# hat_v1.net
KiCad netlist of a schematic drawn in EAGLE
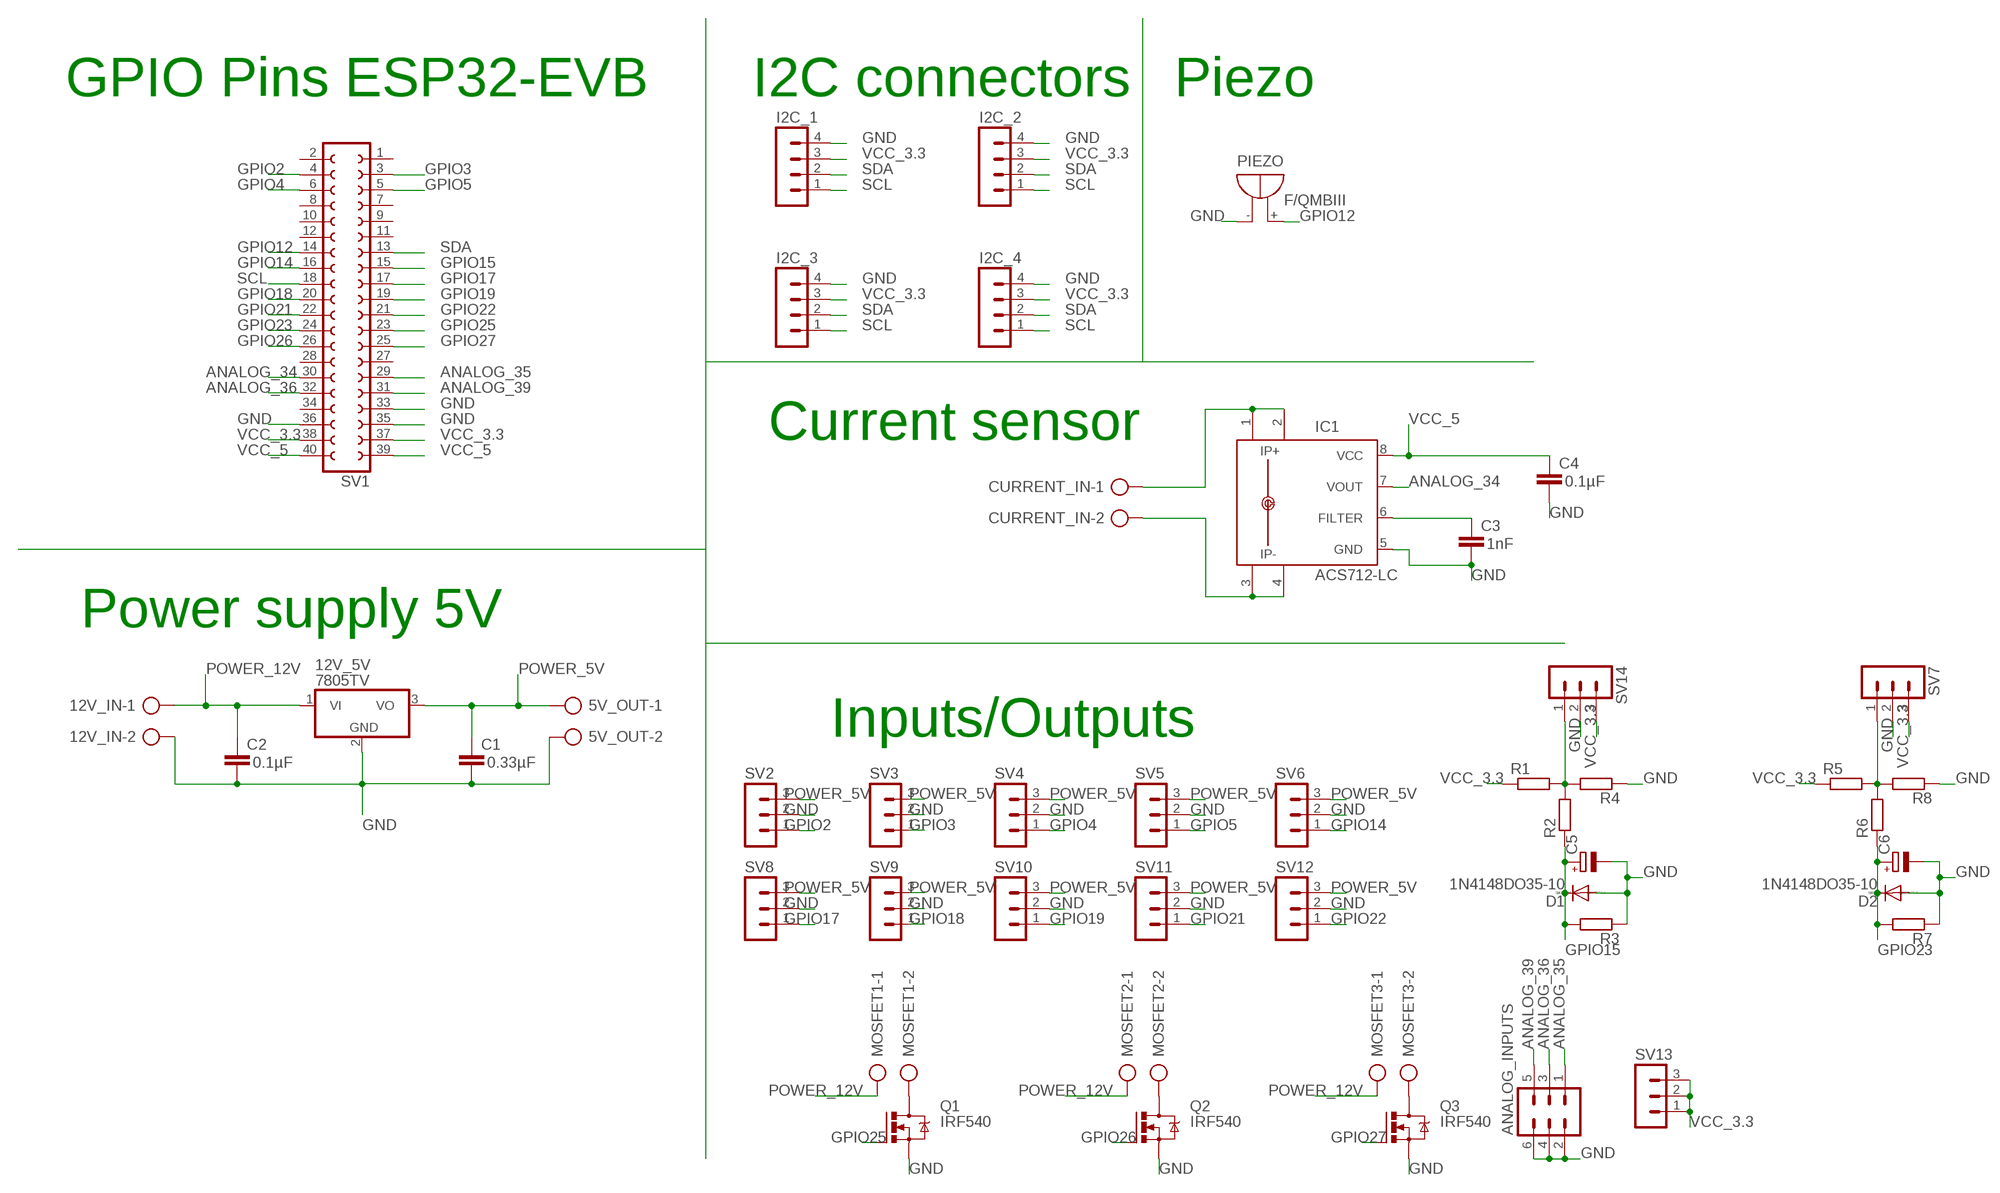
[diagram p0: schematic, sheet 1]

(export (version "E")
  (design (tool "Eeschema 10.0.6"))
  (components
    (comp (ref "5V_OUT")
      (value "AK500/2")
      (footprint "eagle-import:AK500_2")
      (libsource (lib "eagle-import") (part "AK500/2"))
    )
    (comp (ref "12V_5V")
      (value "7805TV")
      (footprint "eagle-import:TO220V")
      (libsource (lib "eagle-import") (part "78TV05"))
    )
    (comp (ref "12V_IN")
      (value "AK500/2")
      (footprint "eagle-import:AK500_2")
      (libsource (lib "eagle-import") (part "AK500/2"))
    )
    (comp (ref "ANALOG_INPUTS")
      (value "MA03-2")
      (footprint "eagle-import:MA03-2")
      (libsource (lib "eagle-import") (part "MA03-2"))
    )
    (comp (ref "C1")
      (value "C-EU050-050X075")
      (footprint "eagle-import:C050-050X075")
      (fields (field (name "C1") "0.33µF"))
      (libsource (lib "eagle-import") (part "resistor_348_C-EU050-050X075"))
    )
    (comp (ref "C2")
      (value "C-EU050-035X075")
      (footprint "eagle-import:C050-035X075")
      (fields (field (name "C2") "0.1µF"))
      (libsource (lib "eagle-import") (part "resistor_348_C-EU050-035X075"))
    )
    (comp (ref "C3")
      (value "C-EU025-025X050")
      (footprint "eagle-import:C025-025X050")
      (fields (field (name "SPICEPREFIX") "C") (field (name "SPICEPREFIX_1") "1nF"))
      (libsource (lib "eagle-import") (part "C-EU025-025X050"))
    )
    (comp (ref "C4")
      (value "C-EU025-025X050")
      (footprint "eagle-import:C025-025X050")
      (fields (field (name "SPICEPREFIX") "C") (field (name "SPICEPREFIX_1") "0.1µF"))
      (libsource (lib "eagle-import") (part "C-EU025-025X050"))
    )
    (comp (ref "C5")
      (value "CPOL-EUE2.5-6")
      (footprint "eagle-import:E2,5-6")
      (libsource (lib "eagle-import") (part "CPOL-EUE2.5-6"))
    )
    (comp (ref "C6")
      (value "CPOL-EUE2.5-6")
      (footprint "eagle-import:E2,5-6")
      (libsource (lib "eagle-import") (part "CPOL-EUE2.5-6"))
    )
    (comp (ref "CURRENT_IN")
      (value "AK500/2")
      (footprint "eagle-import:AK500_2")
      (libsource (lib "eagle-import") (part "AK500/2"))
    )
    (comp (ref "D1")
      (value "1N4148DO35-10")
      (footprint "eagle-import:DO35-10")
      (libsource (lib "eagle-import") (part "1N4148DO35-10"))
    )
    (comp (ref "D2")
      (value "1N4148DO35-10")
      (footprint "eagle-import:DO35-10")
      (libsource (lib "eagle-import") (part "1N4148DO35-10"))
    )
    (comp (ref "I2C_1")
      (value "MA04-1")
      (footprint "eagle-import:MA04-1")
      (libsource (lib "eagle-import") (part "MA04-1"))
    )
    (comp (ref "I2C_2")
      (value "MA04-1")
      (footprint "eagle-import:MA04-1")
      (libsource (lib "eagle-import") (part "MA04-1"))
    )
    (comp (ref "I2C_3")
      (value "MA04-1")
      (footprint "eagle-import:MA04-1")
      (libsource (lib "eagle-import") (part "MA04-1"))
    )
    (comp (ref "I2C_4")
      (value "MA04-1")
      (footprint "eagle-import:MA04-1")
      (libsource (lib "eagle-import") (part "MA04-1"))
    )
    (comp (ref "IC1")
      (value "ACS712-LC")
      (footprint "eagle-import:SOIC8")
      (libsource (lib "eagle-import") (part "ACS712-LC"))
    )
    (comp (ref "MOSFET1")
      (value "AK500/2")
      (footprint "eagle-import:AK500_2")
      (libsource (lib "eagle-import") (part "AK500/2"))
    )
    (comp (ref "MOSFET2")
      (value "AK500/2")
      (footprint "eagle-import:AK500_2")
      (libsource (lib "eagle-import") (part "AK500/2"))
    )
    (comp (ref "MOSFET3")
      (value "AK500/2")
      (footprint "eagle-import:AK500_2")
      (libsource (lib "eagle-import") (part "AK500/2"))
    )
    (comp (ref "PIEZO")
      (value "F/QMBIII")
      (footprint "eagle-import:F_QMBIII")
      (libsource (lib "eagle-import") (part "F/QMBIII"))
    )
    (comp (ref "Q1")
      (value "IRF540")
      (footprint "eagle-import:TO220BV")
      (libsource (lib "eagle-import") (part "IRF540"))
    )
    (comp (ref "Q2")
      (value "IRF540")
      (footprint "eagle-import:TO220BV")
      (libsource (lib "eagle-import") (part "IRF540"))
    )
    (comp (ref "Q3")
      (value "IRF540")
      (footprint "eagle-import:TO220BV")
      (libsource (lib "eagle-import") (part "IRF540"))
    )
    (comp (ref "R1")
      (value "R-EU_0207/2V")
      (footprint "eagle-import:0207_2V")
      (libsource (lib "eagle-import") (part "R-EU_0207/2V"))
    )
    (comp (ref "R2")
      (value "R-EU_0207/2V")
      (footprint "eagle-import:0207_2V")
      (libsource (lib "eagle-import") (part "R-EU_0207/2V"))
    )
    (comp (ref "R3")
      (value "R-EU_0207/2V")
      (footprint "eagle-import:0207_2V")
      (libsource (lib "eagle-import") (part "R-EU_0207/2V"))
    )
    (comp (ref "R4")
      (value "R-EU_0617/5V")
      (footprint "eagle-import:0617V")
      (libsource (lib "eagle-import") (part "R-EU_0617/5V"))
    )
    (comp (ref "R5")
      (value "R-EU_0207/2V")
      (footprint "eagle-import:0207_2V")
      (libsource (lib "eagle-import") (part "R-EU_0207/2V"))
    )
    (comp (ref "R6")
      (value "R-EU_0207/2V")
      (footprint "eagle-import:0207_2V")
      (libsource (lib "eagle-import") (part "R-EU_0207/2V"))
    )
    (comp (ref "R7")
      (value "R-EU_0207/2V")
      (footprint "eagle-import:0207_2V")
      (libsource (lib "eagle-import") (part "R-EU_0207/2V"))
    )
    (comp (ref "R8")
      (value "R-EU_0617/5V")
      (footprint "eagle-import:0617V")
      (libsource (lib "eagle-import") (part "R-EU_0617/5V"))
    )
    (comp (ref "SV1")
      (value "FE20-2")
      (footprint "eagle-import:FE20-2")
      (libsource (lib "eagle-import") (part "FE20-2"))
    )
    (comp (ref "SV2")
      (value "MA03-1")
      (footprint "eagle-import:MA03-1")
      (libsource (lib "eagle-import") (part "MA03-1"))
    )
    (comp (ref "SV3")
      (value "MA03-1")
      (footprint "eagle-import:MA03-1")
      (fields (field (name "SPICEPREFIX") "J"))
      (libsource (lib "eagle-import") (part "MA03-1"))
    )
    (comp (ref "SV4")
      (value "MA03-1")
      (footprint "eagle-import:MA03-1")
      (fields (field (name "SPICEPREFIX") "J"))
      (libsource (lib "eagle-import") (part "MA03-1"))
    )
    (comp (ref "SV5")
      (value "MA03-1")
      (footprint "eagle-import:MA03-1")
      (fields (field (name "SPICEPREFIX") "J"))
      (libsource (lib "eagle-import") (part "MA03-1"))
    )
    (comp (ref "SV6")
      (value "MA03-1")
      (footprint "eagle-import:MA03-1")
      (fields (field (name "SPICEPREFIX") "J"))
      (libsource (lib "eagle-import") (part "MA03-1"))
    )
    (comp (ref "SV7")
      (value "MA03-1")
      (footprint "eagle-import:MA03-1")
      (fields (field (name "SPICEPREFIX") "J"))
      (libsource (lib "eagle-import") (part "MA03-1"))
    )
    (comp (ref "SV8")
      (value "MA03-1")
      (footprint "eagle-import:MA03-1")
      (libsource (lib "eagle-import") (part "MA03-1"))
    )
    (comp (ref "SV9")
      (value "MA03-1")
      (footprint "eagle-import:MA03-1")
      (fields (field (name "SPICEPREFIX") "J"))
      (libsource (lib "eagle-import") (part "MA03-1"))
    )
    (comp (ref "SV10")
      (value "MA03-1")
      (footprint "eagle-import:MA03-1")
      (fields (field (name "SPICEPREFIX") "J"))
      (libsource (lib "eagle-import") (part "MA03-1"))
    )
    (comp (ref "SV11")
      (value "MA03-1")
      (footprint "eagle-import:MA03-1")
      (fields (field (name "SPICEPREFIX") "J"))
      (libsource (lib "eagle-import") (part "MA03-1"))
    )
    (comp (ref "SV12")
      (value "MA03-1")
      (footprint "eagle-import:MA03-1")
      (fields (field (name "SPICEPREFIX") "J"))
      (libsource (lib "eagle-import") (part "MA03-1"))
    )
    (comp (ref "SV13")
      (value "MA03-1")
      (footprint "eagle-import:MA03-1")
      (libsource (lib "eagle-import") (part "MA03-1"))
    )
    (comp (ref "SV14")
      (value "MA03-1")
      (footprint "eagle-import:MA03-1")
      (fields (field (name "SPICEPREFIX") "J"))
      (libsource (lib "eagle-import") (part "MA03-1"))
    )
  )
  (nets
    (net (code "1") (name "/ANALOG_34") (class "Default")
      (node (ref "IC1") (pin "7") (pinfunction "VOUT_7") (pintype "output"))
      (node (ref "SV1") (pin "30") (pinfunction "30_30") (pintype "passive"))
    )
    (net (code "2") (name "/ANALOG_35") (class "Default")
      (node (ref "ANALOG_INPUTS") (pin "1") (pinfunction "1_1") (pintype "passive"))
      (node (ref "SV1") (pin "29") (pinfunction "29_29") (pintype "passive"))
    )
    (net (code "3") (name "/ANALOG_36") (class "Default")
      (node (ref "ANALOG_INPUTS") (pin "3") (pinfunction "3_3") (pintype "passive"))
      (node (ref "SV1") (pin "32") (pinfunction "32_32") (pintype "passive"))
    )
    (net (code "4") (name "/ANALOG_39") (class "Default")
      (node (ref "ANALOG_INPUTS") (pin "5") (pinfunction "5_5") (pintype "passive"))
      (node (ref "SV1") (pin "31") (pinfunction "31_31") (pintype "passive"))
    )
    (net (code "5") (name "/GND") (class "Default")
      (node (ref "12V_5V") (pin "2") (pinfunction "GND_2") (pintype "passive"))
      (node (ref "12V_IN") (pin "2") (pinfunction "KL_2") (pintype "passive"))
      (node (ref "5V_OUT") (pin "2") (pinfunction "KL_2") (pintype "passive"))
      (node (ref "ANALOG_INPUTS") (pin "2") (pinfunction "2_2") (pintype "passive"))
      (node (ref "ANALOG_INPUTS") (pin "4") (pinfunction "4_4") (pintype "passive"))
      (node (ref "ANALOG_INPUTS") (pin "6") (pinfunction "6_6") (pintype "passive"))
      (node (ref "C1") (pin "2") (pinfunction "2_2") (pintype "passive"))
      (node (ref "C2") (pin "2") (pinfunction "2_2") (pintype "passive"))
      (node (ref "C3") (pin "2") (pinfunction "2_2") (pintype "passive"))
      (node (ref "C4") (pin "2") (pinfunction "2_2") (pintype "passive"))
      (node (ref "C5") (pin "-") (pinfunction "-_-") (pintype "passive"))
      (node (ref "C6") (pin "-") (pinfunction "-_-") (pintype "passive"))
      (node (ref "D1") (pin "A") (pinfunction "A_A") (pintype "passive"))
      (node (ref "D2") (pin "A") (pinfunction "A_A") (pintype "passive"))
      (node (ref "I2C_1") (pin "4") (pinfunction "4_4") (pintype "passive"))
      (node (ref "I2C_2") (pin "4") (pinfunction "4_4") (pintype "passive"))
      (node (ref "I2C_3") (pin "4") (pinfunction "4_4") (pintype "passive"))
      (node (ref "I2C_4") (pin "4") (pinfunction "4_4") (pintype "passive"))
      (node (ref "IC1") (pin "5") (pinfunction "GND_5") (pintype "power_in"))
      (node (ref "PIEZO") (pin "-") (pinfunction "+_-") (pintype "passive"))
      (node (ref "Q1") (pin "S") (pinfunction "S_S") (pintype "passive"))
      (node (ref "Q2") (pin "S") (pinfunction "S_S") (pintype "passive"))
      (node (ref "Q3") (pin "S") (pinfunction "S_S") (pintype "passive"))
      (node (ref "R3") (pin "1") (pinfunction "1_1") (pintype "passive"))
      (node (ref "R4") (pin "1") (pinfunction "1_1") (pintype "passive"))
      (node (ref "R7") (pin "1") (pinfunction "1_1") (pintype "passive"))
      (node (ref "R8") (pin "1") (pinfunction "1_1") (pintype "passive"))
      (node (ref "SV1") (pin "33") (pinfunction "33_33") (pintype "passive"))
      (node (ref "SV1") (pin "35") (pinfunction "35_35") (pintype "passive"))
      (node (ref "SV1") (pin "36") (pinfunction "36_36") (pintype "passive"))
      (node (ref "SV10") (pin "2") (pinfunction "2_2") (pintype "passive"))
      (node (ref "SV11") (pin "2") (pinfunction "2_2") (pintype "passive"))
      (node (ref "SV12") (pin "2") (pinfunction "2_2") (pintype "passive"))
      (node (ref "SV14") (pin "2") (pinfunction "2_2") (pintype "passive"))
      (node (ref "SV2") (pin "2") (pinfunction "2_2") (pintype "passive"))
      (node (ref "SV3") (pin "2") (pinfunction "2_2") (pintype "passive"))
      (node (ref "SV4") (pin "2") (pinfunction "2_2") (pintype "passive"))
      (node (ref "SV5") (pin "2") (pinfunction "2_2") (pintype "passive"))
      (node (ref "SV6") (pin "2") (pinfunction "2_2") (pintype "passive"))
      (node (ref "SV7") (pin "2") (pinfunction "2_2") (pintype "passive"))
      (node (ref "SV8") (pin "2") (pinfunction "2_2") (pintype "passive"))
      (node (ref "SV9") (pin "2") (pinfunction "2_2") (pintype "passive"))
    )
    (net (code "6") (name "/GPIO2") (class "Default")
      (node (ref "SV1") (pin "4") (pinfunction "4_4") (pintype "passive"))
      (node (ref "SV2") (pin "1") (pinfunction "1_1") (pintype "passive"))
    )
    (net (code "7") (name "/GPIO3") (class "Default")
      (node (ref "SV1") (pin "3") (pinfunction "3_3") (pintype "passive"))
      (node (ref "SV3") (pin "1") (pinfunction "1_1") (pintype "passive"))
    )
    (net (code "8") (name "/GPIO4") (class "Default")
      (node (ref "SV1") (pin "6") (pinfunction "6_6") (pintype "passive"))
      (node (ref "SV4") (pin "1") (pinfunction "1_1") (pintype "passive"))
    )
    (net (code "9") (name "/GPIO5") (class "Default")
      (node (ref "SV1") (pin "5") (pinfunction "5_5") (pintype "passive"))
      (node (ref "SV5") (pin "1") (pinfunction "1_1") (pintype "passive"))
    )
    (net (code "10") (name "/GPIO12") (class "Default")
      (node (ref "PIEZO") (pin "+") (pinfunction "-_+") (pintype "passive"))
      (node (ref "SV1") (pin "14") (pinfunction "14_14") (pintype "passive"))
    )
    (net (code "11") (name "/GPIO14") (class "Default")
      (node (ref "SV1") (pin "16") (pinfunction "16_16") (pintype "passive"))
      (node (ref "SV6") (pin "1") (pinfunction "1_1") (pintype "passive"))
    )
    (net (code "12") (name "/GPIO15") (class "Default")
      (node (ref "C5") (pin "+") (pinfunction "+_+") (pintype "passive"))
      (node (ref "D1") (pin "C") (pinfunction "C_C") (pintype "passive"))
      (node (ref "R2") (pin "1") (pinfunction "1_1") (pintype "passive"))
      (node (ref "R3") (pin "2") (pinfunction "2_2") (pintype "passive"))
      (node (ref "SV1") (pin "15") (pinfunction "15_15") (pintype "passive"))
    )
    (net (code "13") (name "/GPIO17") (class "Default")
      (node (ref "SV1") (pin "17") (pinfunction "17_17") (pintype "passive"))
      (node (ref "SV8") (pin "1") (pinfunction "1_1") (pintype "passive"))
    )
    (net (code "14") (name "/GPIO18") (class "Default")
      (node (ref "SV1") (pin "20") (pinfunction "20_20") (pintype "passive"))
      (node (ref "SV9") (pin "1") (pinfunction "1_1") (pintype "passive"))
    )
    (net (code "15") (name "/GPIO19") (class "Default")
      (node (ref "SV1") (pin "19") (pinfunction "19_19") (pintype "passive"))
      (node (ref "SV10") (pin "1") (pinfunction "1_1") (pintype "passive"))
    )
    (net (code "16") (name "/GPIO21") (class "Default")
      (node (ref "SV1") (pin "22") (pinfunction "22_22") (pintype "passive"))
      (node (ref "SV11") (pin "1") (pinfunction "1_1") (pintype "passive"))
    )
    (net (code "17") (name "/GPIO22") (class "Default")
      (node (ref "SV1") (pin "21") (pinfunction "21_21") (pintype "passive"))
      (node (ref "SV12") (pin "1") (pinfunction "1_1") (pintype "passive"))
    )
    (net (code "18") (name "/GPIO23") (class "Default")
      (node (ref "C6") (pin "+") (pinfunction "+_+") (pintype "passive"))
      (node (ref "D2") (pin "C") (pinfunction "C_C") (pintype "passive"))
      (node (ref "R6") (pin "1") (pinfunction "1_1") (pintype "passive"))
      (node (ref "R7") (pin "2") (pinfunction "2_2") (pintype "passive"))
      (node (ref "SV1") (pin "24") (pinfunction "24_24") (pintype "passive"))
    )
    (net (code "19") (name "/GPIO25") (class "Default")
      (node (ref "Q1") (pin "G") (pinfunction "G_G") (pintype "passive"))
      (node (ref "SV1") (pin "23") (pinfunction "23_23") (pintype "passive"))
    )
    (net (code "20") (name "/GPIO26") (class "Default")
      (node (ref "Q2") (pin "G") (pinfunction "G_G") (pintype "passive"))
      (node (ref "SV1") (pin "26") (pinfunction "26_26") (pintype "passive"))
    )
    (net (code "21") (name "/GPIO27") (class "Default")
      (node (ref "Q3") (pin "G") (pinfunction "G_G") (pintype "passive"))
      (node (ref "SV1") (pin "25") (pinfunction "25_25") (pintype "passive"))
    )
    (net (code "22") (name "/POWER_5V") (class "Default")
      (node (ref "12V_5V") (pin "3") (pinfunction "VO_3") (pintype "passive"))
      (node (ref "5V_OUT") (pin "1") (pinfunction "KL_1") (pintype "passive"))
      (node (ref "C1") (pin "1") (pinfunction "1_1") (pintype "passive"))
      (node (ref "SV10") (pin "3") (pinfunction "3_3") (pintype "passive"))
      (node (ref "SV11") (pin "3") (pinfunction "3_3") (pintype "passive"))
      (node (ref "SV12") (pin "3") (pinfunction "3_3") (pintype "passive"))
      (node (ref "SV2") (pin "3") (pinfunction "3_3") (pintype "passive"))
      (node (ref "SV3") (pin "3") (pinfunction "3_3") (pintype "passive"))
      (node (ref "SV4") (pin "3") (pinfunction "3_3") (pintype "passive"))
      (node (ref "SV5") (pin "3") (pinfunction "3_3") (pintype "passive"))
      (node (ref "SV6") (pin "3") (pinfunction "3_3") (pintype "passive"))
      (node (ref "SV8") (pin "3") (pinfunction "3_3") (pintype "passive"))
      (node (ref "SV9") (pin "3") (pinfunction "3_3") (pintype "passive"))
    )
    (net (code "23") (name "/POWER_12V") (class "Default")
      (node (ref "12V_5V") (pin "1") (pinfunction "VI_1") (pintype "input"))
      (node (ref "12V_IN") (pin "1") (pinfunction "KL_1") (pintype "passive"))
      (node (ref "C2") (pin "1") (pinfunction "1_1") (pintype "passive"))
      (node (ref "MOSFET1") (pin "1") (pinfunction "KL_1") (pintype "passive"))
      (node (ref "MOSFET2") (pin "1") (pinfunction "KL_1") (pintype "passive"))
      (node (ref "MOSFET3") (pin "1") (pinfunction "KL_1") (pintype "passive"))
    )
    (net (code "24") (name "/SCL") (class "Default")
      (node (ref "I2C_1") (pin "1") (pinfunction "1_1") (pintype "passive"))
      (node (ref "I2C_2") (pin "1") (pinfunction "1_1") (pintype "passive"))
      (node (ref "I2C_3") (pin "1") (pinfunction "1_1") (pintype "passive"))
      (node (ref "I2C_4") (pin "1") (pinfunction "1_1") (pintype "passive"))
      (node (ref "SV1") (pin "18") (pinfunction "18_18") (pintype "passive"))
    )
    (net (code "25") (name "/SDA") (class "Default")
      (node (ref "I2C_1") (pin "2") (pinfunction "2_2") (pintype "passive"))
      (node (ref "I2C_2") (pin "2") (pinfunction "2_2") (pintype "passive"))
      (node (ref "I2C_3") (pin "2") (pinfunction "2_2") (pintype "passive"))
      (node (ref "I2C_4") (pin "2") (pinfunction "2_2") (pintype "passive"))
      (node (ref "SV1") (pin "13") (pinfunction "13_13") (pintype "passive"))
    )
    (net (code "26") (name "/VCC_3.3") (class "Default")
      (node (ref "I2C_1") (pin "3") (pinfunction "3_3") (pintype "passive"))
      (node (ref "I2C_2") (pin "3") (pinfunction "3_3") (pintype "passive"))
      (node (ref "I2C_3") (pin "3") (pinfunction "3_3") (pintype "passive"))
      (node (ref "I2C_4") (pin "3") (pinfunction "3_3") (pintype "passive"))
      (node (ref "R1") (pin "1") (pinfunction "1_1") (pintype "passive"))
      (node (ref "R5") (pin "1") (pinfunction "1_1") (pintype "passive"))
      (node (ref "SV1") (pin "37") (pinfunction "37_37") (pintype "passive"))
      (node (ref "SV1") (pin "38") (pinfunction "38_38") (pintype "passive"))
      (node (ref "SV13") (pin "1") (pinfunction "1_1") (pintype "passive"))
      (node (ref "SV13") (pin "2") (pinfunction "2_2") (pintype "passive"))
      (node (ref "SV13") (pin "3") (pinfunction "3_3") (pintype "passive"))
      (node (ref "SV14") (pin "3") (pinfunction "3_3") (pintype "passive"))
      (node (ref "SV7") (pin "3") (pinfunction "3_3") (pintype "passive"))
    )
    (net (code "27") (name "/VCC_5") (class "Default")
      (node (ref "C4") (pin "1") (pinfunction "1_1") (pintype "passive"))
      (node (ref "IC1") (pin "8") (pinfunction "VCC_8") (pintype "power_in"))
      (node (ref "SV1") (pin "39") (pinfunction "39_39") (pintype "passive"))
      (node (ref "SV1") (pin "40") (pinfunction "40_40") (pintype "passive"))
    )
    (net (code "28") (name "Net-(CURRENT_INA-KL)") (class "Default")
      (node (ref "CURRENT_IN") (pin "1") (pinfunction "KL_1") (pintype "passive"))
      (node (ref "IC1") (pin "1") (pinfunction "IP+_1") (pintype "passive"))
      (node (ref "IC1") (pin "2") (pinfunction "IP+1_2") (pintype "passive"))
    )
    (net (code "29") (name "Net-(CURRENT_INB-KL)") (class "Default")
      (node (ref "CURRENT_IN") (pin "2") (pinfunction "KL_2") (pintype "passive"))
      (node (ref "IC1") (pin "3") (pinfunction "IP-_3") (pintype "passive"))
      (node (ref "IC1") (pin "4") (pinfunction "IP-1_4") (pintype "passive"))
    )
    (net (code "30") (name "Net-(IC1-FILTER)") (class "Default")
      (node (ref "C3") (pin "1") (pinfunction "1_1") (pintype "passive"))
      (node (ref "IC1") (pin "6") (pinfunction "FILTER_6") (pintype "bidirectional"))
    )
    (net (code "31") (name "Net-(MOSFET1B-KL)") (class "Default")
      (node (ref "MOSFET1") (pin "2") (pinfunction "KL_2") (pintype "passive"))
      (node (ref "Q1") (pin "D") (pinfunction "D_D") (pintype "passive"))
    )
    (net (code "32") (name "Net-(MOSFET2B-KL)") (class "Default")
      (node (ref "MOSFET2") (pin "2") (pinfunction "KL_2") (pintype "passive"))
      (node (ref "Q2") (pin "D") (pinfunction "D_D") (pintype "passive"))
    )
    (net (code "33") (name "Net-(MOSFET3B-KL)") (class "Default")
      (node (ref "MOSFET3") (pin "2") (pinfunction "KL_2") (pintype "passive"))
      (node (ref "Q3") (pin "D") (pinfunction "D_D") (pintype "passive"))
    )
    (net (code "34") (name "Net-(R1-Pad2)") (class "Default")
      (node (ref "R1") (pin "2") (pinfunction "2_2") (pintype "passive"))
      (node (ref "R2") (pin "2") (pinfunction "2_2") (pintype "passive"))
      (node (ref "R4") (pin "2") (pinfunction "2_2") (pintype "passive"))
      (node (ref "SV14") (pin "1") (pinfunction "1_1") (pintype "passive"))
    )
    (net (code "35") (name "Net-(R5-Pad2)") (class "Default")
      (node (ref "R5") (pin "2") (pinfunction "2_2") (pintype "passive"))
      (node (ref "R6") (pin "2") (pinfunction "2_2") (pintype "passive"))
      (node (ref "R8") (pin "2") (pinfunction "2_2") (pintype "passive"))
      (node (ref "SV7") (pin "1") (pinfunction "1_1") (pintype "passive"))
    )
    (net (code "36") (name "unconnected-(SV1-Pad1)") (class "Default")
      (node (ref "SV1") (pin "1") (pinfunction "1_1") (pintype "passive"))
    )
    (net (code "37") (name "unconnected-(SV1-Pad2)") (class "Default")
      (node (ref "SV1") (pin "2") (pinfunction "2_2") (pintype "passive"))
    )
    (net (code "38") (name "unconnected-(SV1-Pad7)") (class "Default")
      (node (ref "SV1") (pin "7") (pinfunction "7_7") (pintype "passive"))
    )
    (net (code "39") (name "unconnected-(SV1-Pad8)") (class "Default")
      (node (ref "SV1") (pin "8") (pinfunction "8_8") (pintype "passive"))
    )
    (net (code "40") (name "unconnected-(SV1-Pad9)") (class "Default")
      (node (ref "SV1") (pin "9") (pinfunction "9_9") (pintype "passive"))
    )
    (net (code "41") (name "unconnected-(SV1-Pad10)") (class "Default")
      (node (ref "SV1") (pin "10") (pinfunction "10_10") (pintype "passive"))
    )
    (net (code "42") (name "unconnected-(SV1-Pad11)") (class "Default")
      (node (ref "SV1") (pin "11") (pinfunction "11_11") (pintype "passive"))
    )
    (net (code "43") (name "unconnected-(SV1-Pad12)") (class "Default")
      (node (ref "SV1") (pin "12") (pinfunction "12_12") (pintype "passive"))
    )
    (net (code "44") (name "unconnected-(SV1-Pad27)") (class "Default")
      (node (ref "SV1") (pin "27") (pinfunction "27_27") (pintype "passive"))
    )
    (net (code "45") (name "unconnected-(SV1-Pad28)") (class "Default")
      (node (ref "SV1") (pin "28") (pinfunction "28_28") (pintype "passive"))
    )
    (net (code "46") (name "unconnected-(SV1-Pad34)") (class "Default")
      (node (ref "SV1") (pin "34") (pinfunction "34_34") (pintype "passive"))
    )
  )
)
